# Power_Board.net
KiCad netlist of a schematic drawn in EAGLE
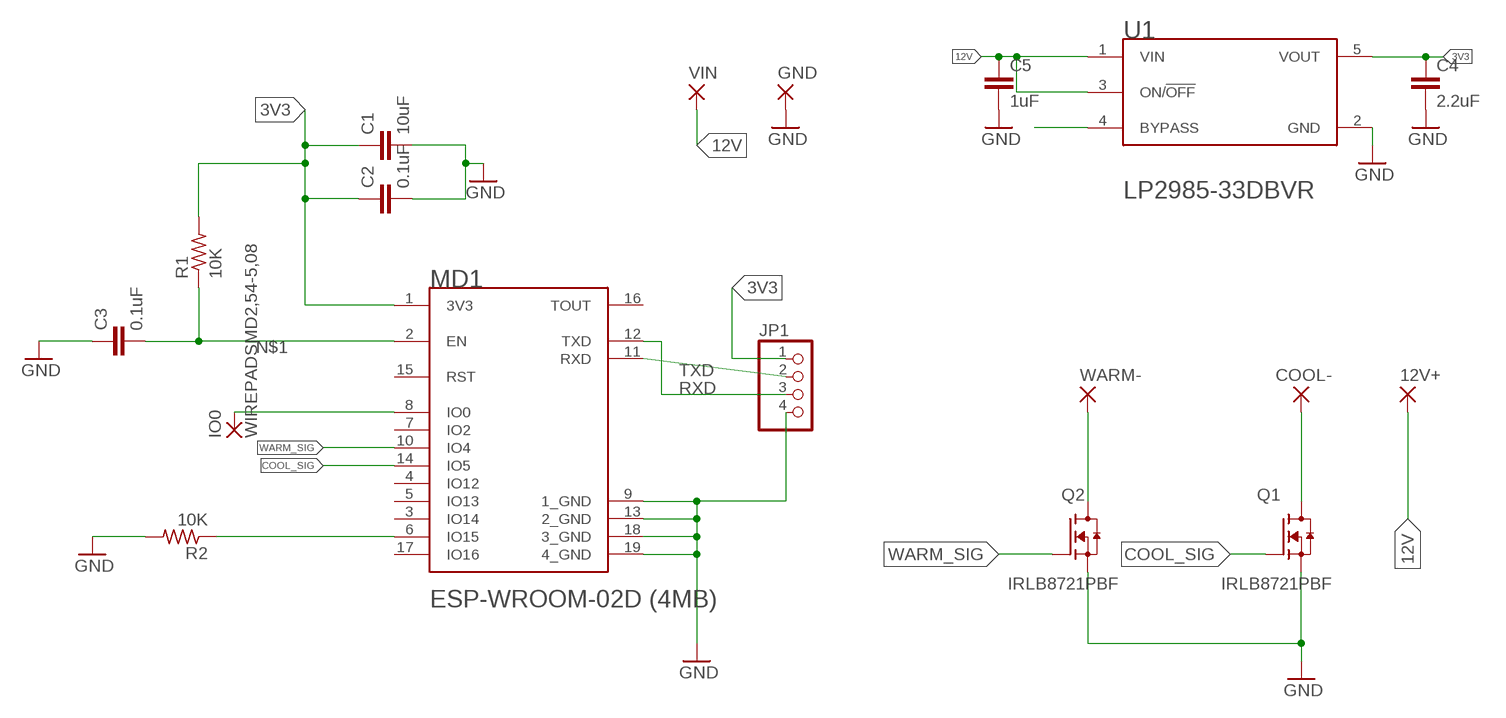
[diagram p0: schematic, sheet 1]

(export (version "E")
  (design (tool "Eeschema 10.0.6"))
  (components
    (comp (ref "12V+")
      (value "WIREPADSMD5-2,5")
      (footprint "eagle-import:5-2,5")
      (libsource (lib "eagle-import") (part "WIREPADSMD5-2,5"))
    )
    (comp (ref "C1")
      (value "10uF")
      (footprint "eagle-import:C1206")
      (libsource (lib "eagle-import") (part "C-EUC1206"))
    )
    (comp (ref "C2")
      (value "0.1uF")
      (footprint "eagle-import:C1206")
      (libsource (lib "eagle-import") (part "C-EUC1206"))
    )
    (comp (ref "C3")
      (value "0.1uF")
      (footprint "eagle-import:C1206")
      (libsource (lib "eagle-import") (part "C-EUC1206"))
    )
    (comp (ref "C4")
      (value "2.2uF")
      (footprint "eagle-import:C1206")
      (libsource (lib "eagle-import") (part "C-EUC1206"))
    )
    (comp (ref "C5")
      (value "1uF")
      (footprint "eagle-import:C1206")
      (libsource (lib "eagle-import") (part "C-EUC1206"))
    )
    (comp (ref "COOL-")
      (value "WIREPADSMD5-2,5")
      (footprint "eagle-import:5-2,5")
      (libsource (lib "eagle-import") (part "WIREPADSMD5-2,5"))
    )
    (comp (ref "GND")
      (value "WIREPADSMD5-2,5")
      (footprint "eagle-import:5-2,5")
      (libsource (lib "eagle-import") (part "WIREPADSMD5-2,5"))
    )
    (comp (ref "IO0")
      (value "WIREPADSMD2,54-5,08")
      (footprint "eagle-import:SMD2,54-5,08")
      (libsource (lib "eagle-import") (part "WIREPADSMD2,54-5,08"))
    )
    (comp (ref "JP1")
      (value "PINHD-1X4")
      (footprint "eagle-import:1X04")
      (libsource (lib "eagle-import") (part "PINHD-1X4"))
    )
    (comp (ref "MD1")
      (value "ESPRESSIF_SYSTEMS_ESP-WROOM-02D_4MBESPRESSIF_SYSTEMS_ESP-WROOM-02D_4MB_0_0")
      (footprint "eagle-import:ESPRESSIF_SYSTEMS_ESP-WROOM-02D_4MB_0")
      (fields
        (field (name "DIGIKEY_PART_NUMBER") "1965-ESP-WROOM-02D(4MB)CT-ND")
        (field (name "MF") "Espressif Systems")
        (field (name "MOUSER_PART_NUMBER") "356-ESPWROOM02D(4MB)")
      )
      (libsource (lib "eagle-import") (part "ESPRESSIF_SYSTEMS_ESP-WROOM-02D_4MBESPRESSIF_SYSTEMS_ESP-WROOM-02D_4MB_0_0"))
    )
    (comp (ref "Q1")
      (value "IRLB8721PBF")
      (footprint "eagle-import:TO254P1067X483X2057-3")
      (fields (field (name "MF") "Infineon Technologies"))
      (libsource (lib "eagle-import") (part "IRLB8721PBF"))
    )
    (comp (ref "Q2")
      (value "IRLB8721PBF")
      (footprint "eagle-import:TO254P1067X483X2057-3")
      (fields (field (name "MF") "Infineon Technologies"))
      (libsource (lib "eagle-import") (part "IRLB8721PBF"))
    )
    (comp (ref "R1")
      (value "10K")
      (footprint "eagle-import:R1206")
      (libsource (lib "eagle-import") (part "R-US_R1206"))
    )
    (comp (ref "R2")
      (value "10K")
      (footprint "eagle-import:R1206")
      (libsource (lib "eagle-import") (part "R-US_R1206"))
    )
    (comp (ref "U1")
      (value "TEXAS_INSTRUMENTS_LP2985-33DBVRTEXAS_INSTRUMENTS_LP2985-33DBVR_0_0")
      (footprint "eagle-import:TEXAS_INSTRUMENTS_LP2985-33DBVR_0")
      (fields
        (field (name "DIGIKEY_PART_NUMBER") "296-18476-1-ND")
        (field (name "MF") "Texas Instruments")
        (field (name "MOUSER_PART_NUMBER") "595-LP2985-33DBVR")
      )
      (libsource (lib "eagle-import") (part "TEXAS_INSTRUMENTS_LP2985-33DBVRTEXAS_INSTRUMENTS_LP2985-33DBVR_0_0"))
    )
    (comp (ref "VIN")
      (value "WIREPADSMD5-2,5")
      (footprint "eagle-import:5-2,5")
      (libsource (lib "eagle-import") (part "WIREPADSMD5-2,5"))
    )
    (comp (ref "WARM-")
      (value "WIREPADSMD5-2,5")
      (footprint "eagle-import:5-2,5")
      (libsource (lib "eagle-import") (part "WIREPADSMD5-2,5"))
    )
  )
  (nets
    (net (code "1") (name "/N$1") (class "Default")
      (node (ref "C3") (pin "2") (pinfunction "2_2") (pintype "passive"))
      (node (ref "MD1") (pin "2") (pinfunction "EN_2") (pintype "input"))
      (node (ref "R1") (pin "1") (pinfunction "1_1") (pintype "passive"))
    )
    (net (code "2") (name "/RXD") (class "Default")
      (node (ref "JP1") (pin "2") (pinfunction "2_2") (pintype "passive"))
      (node (ref "MD1") (pin "11") (pinfunction "RXD_11") (pintype "input"))
    )
    (net (code "3") (name "/TXD") (class "Default")
      (node (ref "JP1") (pin "3") (pinfunction "3_3") (pintype "passive"))
      (node (ref "MD1") (pin "12") (pinfunction "TXD_12") (pintype "output"))
    )
    (net (code "4") (name "3V3") (class "Default")
      (node (ref "C1") (pin "1") (pinfunction "1_1") (pintype "passive"))
      (node (ref "C2") (pin "1") (pinfunction "1_1") (pintype "passive"))
      (node (ref "C4") (pin "1") (pinfunction "1_1") (pintype "passive"))
      (node (ref "JP1") (pin "1") (pinfunction "1_1") (pintype "passive"))
      (node (ref "MD1") (pin "1") (pinfunction "3V3_1") (pintype "power_in"))
      (node (ref "R1") (pin "2") (pinfunction "2_2") (pintype "passive"))
      (node (ref "U1") (pin "5") (pinfunction "VOUT_5") (pintype "power_in"))
    )
    (net (code "5") (name "12V") (class "Default")
      (node (ref "12V+") (pin "1") (pinfunction "P_1") (pintype "passive"))
      (node (ref "C5") (pin "1") (pinfunction "1_1") (pintype "passive"))
      (node (ref "U1") (pin "1") (pinfunction "VIN_1") (pintype "power_in"))
      (node (ref "U1") (pin "3") (pinfunction "ON/~{OFF}_3") (pintype "input"))
      (node (ref "VIN") (pin "1") (pinfunction "P_1") (pintype "passive"))
    )
    (net (code "6") (name "COOL_SIG") (class "Default")
      (node (ref "MD1") (pin "14") (pinfunction "IO5_14") (pintype "bidirectional"))
      (node (ref "Q1") (pin "1") (pinfunction "G_1") (pintype "passive"))
    )
    (net (code "7") (name "GND") (class "Default")
      (node (ref "C1") (pin "2") (pinfunction "2_2") (pintype "passive"))
      (node (ref "C2") (pin "2") (pinfunction "2_2") (pintype "passive"))
      (node (ref "C3") (pin "1") (pinfunction "1_1") (pintype "passive"))
      (node (ref "C4") (pin "2") (pinfunction "2_2") (pintype "passive"))
      (node (ref "C5") (pin "2") (pinfunction "2_2") (pintype "passive"))
      (node (ref "GND") (pin "1") (pinfunction "P_1") (pintype "passive"))
      (node (ref "JP1") (pin "4") (pinfunction "4_4") (pintype "passive"))
      (node (ref "MD1") (pin "13") (pinfunction "2_GND_13") (pintype "power_in"))
      (node (ref "MD1") (pin "18") (pinfunction "3_GND_18") (pintype "power_in"))
      (node (ref "MD1") (pin "19") (pinfunction "4_GND_19") (pintype "power_in"))
      (node (ref "MD1") (pin "9") (pinfunction "1_GND_9") (pintype "power_in"))
      (node (ref "Q1") (pin "3") (pinfunction "S_3") (pintype "passive"))
      (node (ref "Q2") (pin "3") (pinfunction "S_3") (pintype "passive"))
      (node (ref "R2") (pin "2") (pinfunction "2_2") (pintype "passive"))
      (node (ref "U1") (pin "2") (pinfunction "GND_2") (pintype "power_in"))
    )
    (net (code "8") (name "Net-(COOL--P)") (class "Default")
      (node (ref "COOL-") (pin "1") (pinfunction "P_1") (pintype "passive"))
      (node (ref "Q1") (pin "2") (pinfunction "D_2") (pintype "passive"))
    )
    (net (code "9") (name "Net-(IO0-P)") (class "Default")
      (node (ref "IO0") (pin "1") (pinfunction "P_1") (pintype "passive"))
      (node (ref "MD1") (pin "8") (pinfunction "IO0_8") (pintype "bidirectional"))
    )
    (net (code "10") (name "Net-(MD1-IO15)") (class "Default")
      (node (ref "MD1") (pin "6") (pinfunction "IO15_6") (pintype "bidirectional"))
      (node (ref "R2") (pin "1") (pinfunction "1_1") (pintype "passive"))
    )
    (net (code "11") (name "Net-(Q2-D)") (class "Default")
      (node (ref "Q2") (pin "2") (pinfunction "D_2") (pintype "passive"))
      (node (ref "WARM-") (pin "1") (pinfunction "P_1") (pintype "passive"))
    )
    (net (code "12") (name "WARM_SIG") (class "Default")
      (node (ref "MD1") (pin "10") (pinfunction "IO4_10") (pintype "bidirectional"))
      (node (ref "Q2") (pin "1") (pinfunction "G_1") (pintype "passive"))
    )
    (net (code "13") (name "unconnected-(MD1-IO2-Pad7)") (class "Default")
      (node (ref "MD1") (pin "7") (pinfunction "IO2_7") (pintype "bidirectional"))
    )
    (net (code "14") (name "unconnected-(MD1-IO12-Pad4)") (class "Default")
      (node (ref "MD1") (pin "4") (pinfunction "IO12_4") (pintype "bidirectional"))
    )
    (net (code "15") (name "unconnected-(MD1-IO13-Pad5)") (class "Default")
      (node (ref "MD1") (pin "5") (pinfunction "IO13_5") (pintype "bidirectional"))
    )
    (net (code "16") (name "unconnected-(MD1-IO14-Pad3)") (class "Default")
      (node (ref "MD1") (pin "3") (pinfunction "IO14_3") (pintype "bidirectional"))
    )
    (net (code "17") (name "unconnected-(MD1-IO16-Pad17)") (class "Default")
      (node (ref "MD1") (pin "17") (pinfunction "IO16_17") (pintype "bidirectional"))
    )
    (net (code "18") (name "unconnected-(MD1-RST-Pad15)") (class "Default")
      (node (ref "MD1") (pin "15") (pinfunction "RST_15") (pintype "input"))
    )
    (net (code "19") (name "unconnected-(MD1-TOUT-Pad16)") (class "Default")
      (node (ref "MD1") (pin "16") (pinfunction "TOUT_16") (pintype "output"))
    )
    (net (code "20") (name "unconnected-(U1-BYPASS-Pad4)") (class "Default")
      (node (ref "U1") (pin "4") (pinfunction "BYPASS_4") (pintype "passive"))
    )
  )
)
